# schematic.net
KiCad netlist of a schematic drawn in EasyEDA
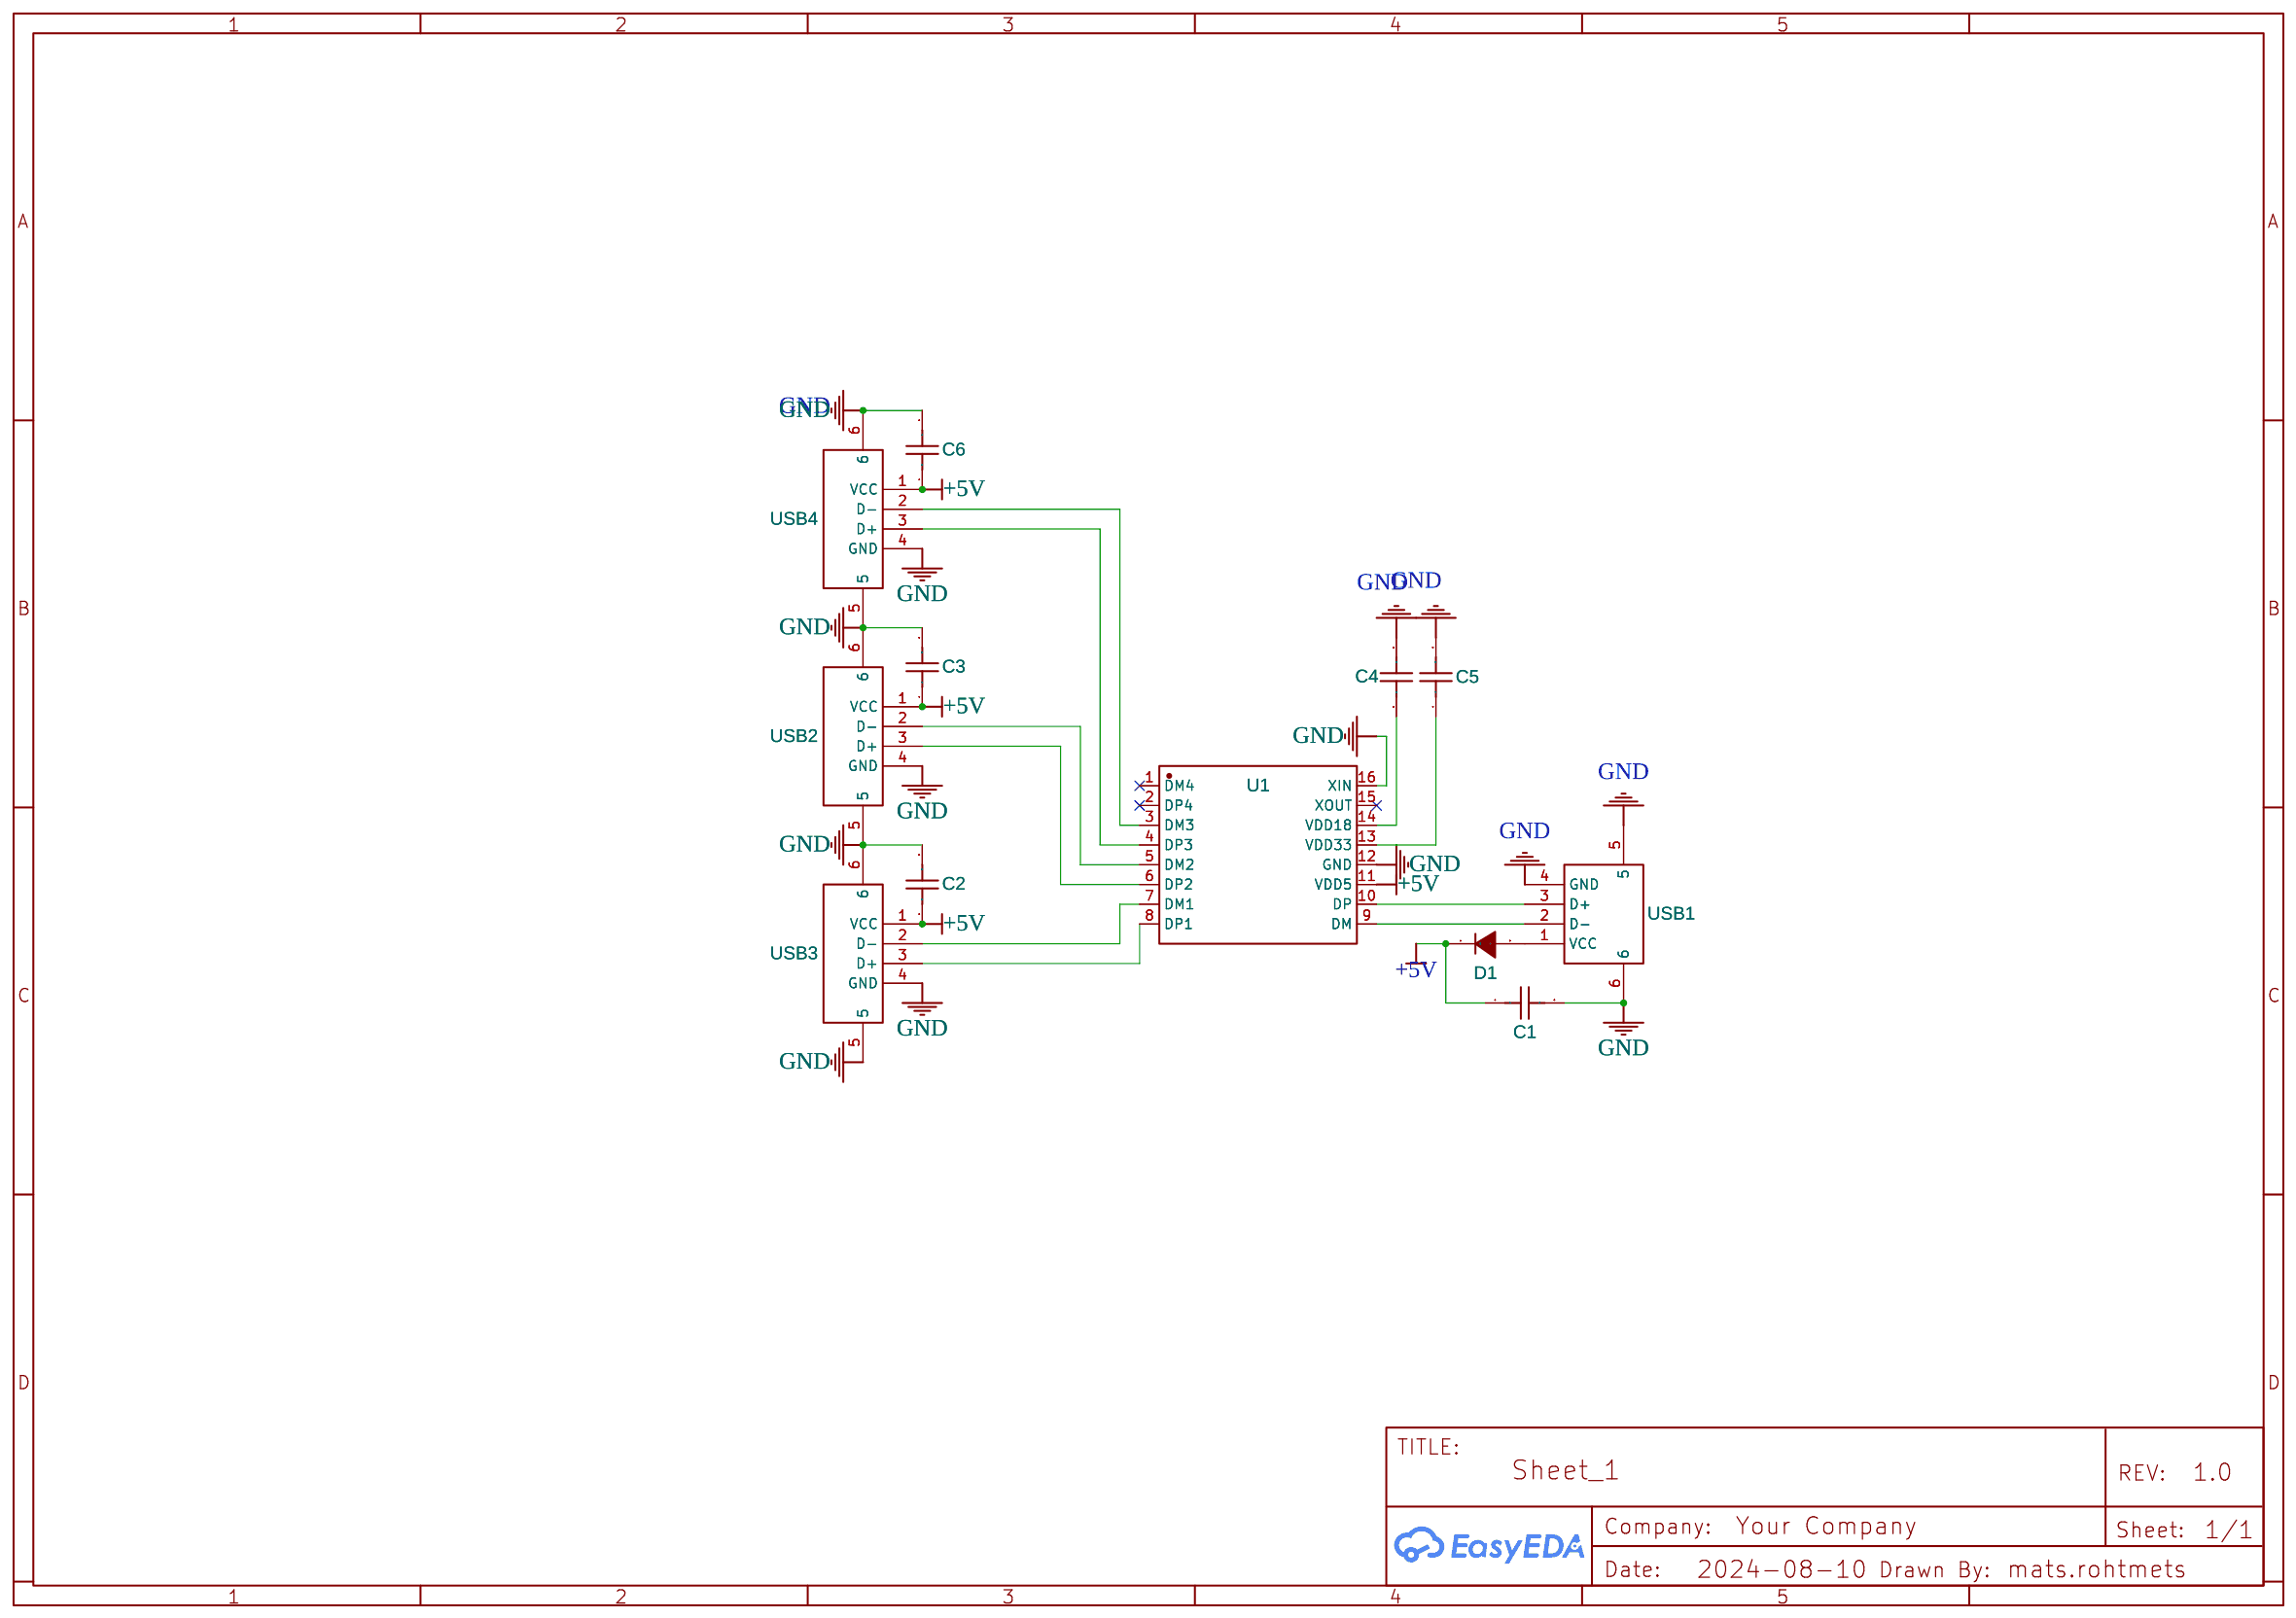
[diagram p0: schematic sheet]

(export (version "E")
  (design (tool "Eeschema 10.0.6"))
  (components
    (comp (ref "C1")
      (value "10uF")
      (fields
        (field (name "Manufacturer Part") "CL10A106KP8NNNC")
        (field (name "Manufacturer") "SAMSUNG(三星)")
      )
      (libsource (lib "") (part "CL10A106KP8NNNC"))
    )
    (comp (ref "C2")
      (value "10uF")
      (fields
        (field (name "Manufacturer Part") "CL10A106KP8NNNC")
        (field (name "Manufacturer") "SAMSUNG(三星)")
      )
      (libsource (lib "") (part "CL10A106KP8NNNC_1"))
    )
    (comp (ref "C3")
      (value "10uF")
      (fields
        (field (name "Manufacturer Part") "CL10A106KP8NNNC")
        (field (name "Manufacturer") "SAMSUNG(三星)")
      )
      (libsource (lib "") (part "CL10A106KP8NNNC_1"))
    )
    (comp (ref "C4")
      (value "10uF")
      (fields
        (field (name "Manufacturer Part") "CL10A106KP8NNNC")
        (field (name "Manufacturer") "SAMSUNG(三星)")
      )
      (libsource (lib "") (part "CL10A106KP8NNNC_1"))
    )
    (comp (ref "C5")
      (value "10uF")
      (fields
        (field (name "Manufacturer Part") "CL10A106KP8NNNC")
        (field (name "Manufacturer") "SAMSUNG(三星)")
      )
      (libsource (lib "") (part "CL10A106KP8NNNC_1"))
    )
    (comp (ref "C6")
      (value "10uF")
      (fields
        (field (name "Manufacturer Part") "CL10A106KP8NNNC")
        (field (name "Manufacturer") "SAMSUNG(三星)")
      )
      (libsource (lib "") (part "CL10A106KP8NNNC_1"))
    )
    (comp (ref "D1")
      (value "NSR0320MW2T1G")
      (fields (field (name "Manufacturer") "onsemi(安森美)"))
      (libsource (lib "") (part "NSR0320MW2T1G"))
    )
    (comp (ref "U1")
      (value "SL2.1A")
      (fields (field (name "Manufacturer") "CoreChips(和芯润德)"))
      (libsource (lib "") (part "SL2.1A"))
    )
    (comp (ref "USB1")
      (value "U-G-04DD-W-01")
      (fields (field (name "Manufacturer Part") "U-G-O4DD-W-1") (field (name "Manufacturer") "韩国韩荣"))
      (libsource (lib "") (part "U-G-04DD-W-01"))
    )
    (comp (ref "USB2")
      (value "USB-AF-90-14.4X13.6-H7.0-DIP")
      (fields (field (name "Manufacturer Part") "903-131A1011D10100") (field (name "Manufacturer") "精拓金"))
      (libsource (lib "") (part "USB-AF-90-14.4X13.6-H7.0-DIP"))
    )
    (comp (ref "USB3")
      (value "USB-AF-90-14.4X13.6-H7.0-DIP")
      (fields (field (name "Manufacturer Part") "903-131A1011D10100") (field (name "Manufacturer") "精拓金"))
      (libsource (lib "") (part "USB-AF-90-14.4X13.6-H7.0-DIP"))
    )
    (comp (ref "USB4")
      (value "USB-AF-90-14.4X13.6-H7.0-DIP")
      (fields (field (name "Manufacturer Part") "903-131A1011D10100") (field (name "Manufacturer") "精拓金"))
      (libsource (lib "") (part "USB-AF-90-14.4X13.6-H7.0-DIP"))
    )
  )
  (nets
    (net (code "1") (name "+5V") (class "Default")
      (node (ref "C1") (pin "1") (pinfunction "1_1") (pintype "unspecified"))
      (node (ref "C2") (pin "1") (pinfunction "1_1") (pintype "unspecified"))
      (node (ref "C3") (pin "1") (pinfunction "1_1") (pintype "unspecified"))
      (node (ref "C6") (pin "1") (pinfunction "1_1") (pintype "unspecified"))
      (node (ref "D1") (pin "1") (pinfunction "C_1") (pintype "unspecified"))
      (node (ref "U1") (pin "11") (pinfunction "VDD5_11") (pintype "unspecified"))
      (node (ref "USB2") (pin "1") (pinfunction "VCC_1") (pintype "unspecified"))
      (node (ref "USB3") (pin "1") (pinfunction "VCC_1") (pintype "unspecified"))
      (node (ref "USB4") (pin "1") (pinfunction "VCC_1") (pintype "unspecified"))
    )
    (net (code "2") (name "GND") (class "Default")
      (node (ref "C1") (pin "2") (pinfunction "2_2") (pintype "unspecified"))
      (node (ref "C2") (pin "2") (pinfunction "2_2") (pintype "unspecified"))
      (node (ref "C3") (pin "2") (pinfunction "2_2") (pintype "unspecified"))
      (node (ref "C4") (pin "2") (pinfunction "2_2") (pintype "unspecified"))
      (node (ref "C5") (pin "2") (pinfunction "2_2") (pintype "unspecified"))
      (node (ref "C6") (pin "2") (pinfunction "2_2") (pintype "unspecified"))
      (node (ref "U1") (pin "12") (pinfunction "GND_12") (pintype "unspecified"))
      (node (ref "U1") (pin "16") (pinfunction "XIN_16") (pintype "unspecified"))
      (node (ref "USB1") (pin "4") (pinfunction "GND_4") (pintype "unspecified"))
      (node (ref "USB1") (pin "5") (pinfunction "5_5") (pintype "unspecified"))
      (node (ref "USB1") (pin "6") (pinfunction "6_6") (pintype "unspecified"))
      (node (ref "USB2") (pin "4") (pinfunction "GND_4") (pintype "unspecified"))
      (node (ref "USB2") (pin "5") (pinfunction "5_5") (pintype "unspecified"))
      (node (ref "USB2") (pin "6") (pinfunction "6_6") (pintype "unspecified"))
      (node (ref "USB3") (pin "4") (pinfunction "GND_4") (pintype "unspecified"))
      (node (ref "USB3") (pin "5") (pinfunction "5_5") (pintype "unspecified"))
      (node (ref "USB3") (pin "6") (pinfunction "6_6") (pintype "unspecified"))
      (node (ref "USB4") (pin "4") (pinfunction "GND_4") (pintype "unspecified"))
      (node (ref "USB4") (pin "5") (pinfunction "5_5") (pintype "unspecified"))
      (node (ref "USB4") (pin "6") (pinfunction "6_6") (pintype "unspecified"))
    )
    (net (code "3") (name "Net-(D1-A)") (class "Default")
      (node (ref "D1") (pin "2") (pinfunction "A_2") (pintype "unspecified"))
      (node (ref "USB1") (pin "1") (pinfunction "VCC_1") (pintype "unspecified"))
    )
    (net (code "4") (name "Net-(U1-DM)") (class "Default")
      (node (ref "U1") (pin "9") (pinfunction "DM_9") (pintype "unspecified"))
      (node (ref "USB1") (pin "2") (pinfunction "D-_2") (pintype "unspecified"))
    )
    (net (code "5") (name "Net-(U1-DM1)") (class "Default")
      (node (ref "U1") (pin "7") (pinfunction "DM1_7") (pintype "unspecified"))
      (node (ref "USB3") (pin "2") (pinfunction "D-_2") (pintype "unspecified"))
    )
    (net (code "6") (name "Net-(U1-DM2)") (class "Default")
      (node (ref "U1") (pin "5") (pinfunction "DM2_5") (pintype "unspecified"))
      (node (ref "USB2") (pin "2") (pinfunction "D-_2") (pintype "unspecified"))
    )
    (net (code "7") (name "Net-(U1-DM3)") (class "Default")
      (node (ref "U1") (pin "3") (pinfunction "DM3_3") (pintype "unspecified"))
      (node (ref "USB4") (pin "2") (pinfunction "D-_2") (pintype "unspecified"))
    )
    (net (code "8") (name "Net-(U1-DP)") (class "Default")
      (node (ref "U1") (pin "10") (pinfunction "DP_10") (pintype "unspecified"))
      (node (ref "USB1") (pin "3") (pinfunction "D+_3") (pintype "unspecified"))
    )
    (net (code "9") (name "Net-(U1-DP1)") (class "Default")
      (node (ref "U1") (pin "8") (pinfunction "DP1_8") (pintype "unspecified"))
      (node (ref "USB3") (pin "3") (pinfunction "D+_3") (pintype "unspecified"))
    )
    (net (code "10") (name "Net-(U1-DP2)") (class "Default")
      (node (ref "U1") (pin "6") (pinfunction "DP2_6") (pintype "unspecified"))
      (node (ref "USB2") (pin "3") (pinfunction "D+_3") (pintype "unspecified"))
    )
    (net (code "11") (name "Net-(U1-DP3)") (class "Default")
      (node (ref "U1") (pin "4") (pinfunction "DP3_4") (pintype "unspecified"))
      (node (ref "USB4") (pin "3") (pinfunction "D+_3") (pintype "unspecified"))
    )
    (net (code "12") (name "Net-(U1-VDD18)") (class "Default")
      (node (ref "C4") (pin "1") (pinfunction "1_1") (pintype "unspecified"))
      (node (ref "U1") (pin "14") (pinfunction "VDD18_14") (pintype "unspecified"))
    )
    (net (code "13") (name "Net-(U1-VDD33)") (class "Default")
      (node (ref "C5") (pin "1") (pinfunction "1_1") (pintype "unspecified"))
      (node (ref "U1") (pin "13") (pinfunction "VDD33_13") (pintype "unspecified"))
    )
    (net (code "14") (name "unconnected-(U1-DM4-Pad1)") (class "Default")
      (node (ref "U1") (pin "1") (pinfunction "DM4_1") (pintype "unspecified+no_connect"))
    )
    (net (code "15") (name "unconnected-(U1-DP4-Pad2)") (class "Default")
      (node (ref "U1") (pin "2") (pinfunction "DP4_2") (pintype "unspecified+no_connect"))
    )
    (net (code "16") (name "unconnected-(U1-XOUT-Pad15)") (class "Default")
      (node (ref "U1") (pin "15") (pinfunction "XOUT_15") (pintype "unspecified+no_connect"))
    )
  )
)
